# plugFeather.net
KiCad netlist of a schematic drawn in EAGLE
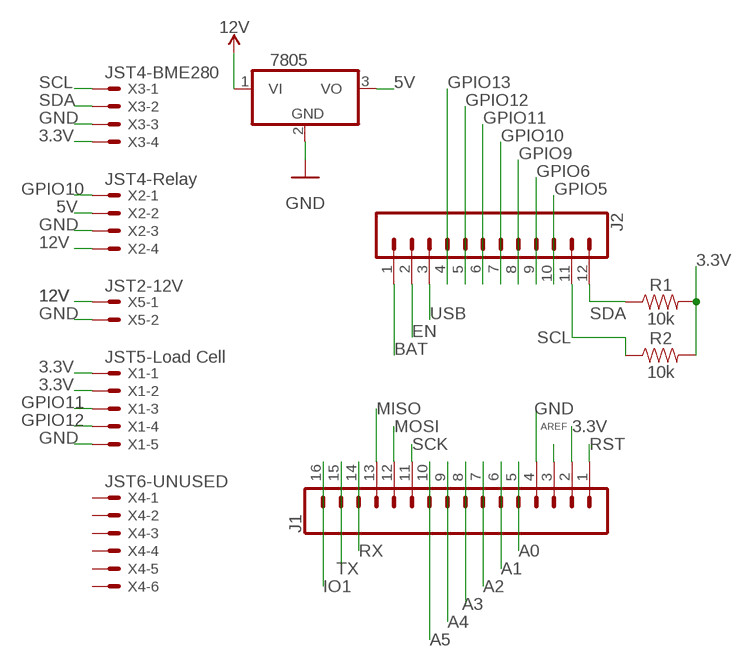
[diagram p0: schematic, sheet 1]

(export (version "E")
  (design (tool "Eeschema 10.0.6"))
  (components
    (comp (ref "IC1")
      (value "7805")
      (footprint "eagle-import:TO220V")
      (libsource (lib "eagle-import") (part "78TV05"))
    )
    (comp (ref "J1")
      (value "CONN_16")
      (footprint "eagle-import:1X16")
      (libsource (lib "eagle-import") (part "CONN_16"))
    )
    (comp (ref "J2")
      (value "CONN_12")
      (footprint "eagle-import:1X12")
      (libsource (lib "eagle-import") (part "CONN_12"))
    )
    (comp (ref "R1")
      (value "10k")
      (footprint "eagle-import:AXIAL-0.3")
      (libsource (lib "eagle-import") (part "10KOHM-HORIZ-1/4W-5%"))
    )
    (comp (ref "R2")
      (value "10k")
      (footprint "eagle-import:AXIAL-0.3")
      (libsource (lib "eagle-import") (part "10KOHM-HORIZ-1/4W-5%"))
    )
    (comp (ref "X1")
      (value "JST5-Load Cell")
      (footprint "eagle-import:JST-XH-05-PACKAGE-LONG-PAD")
      (libsource (lib "eagle-import") (part "JST-XH-05-PIN-LONG-PAD"))
    )
    (comp (ref "X2")
      (value "JST4-Relay")
      (footprint "eagle-import:JST-XH-04-PACKAGE-LONG-PAD")
      (libsource (lib "eagle-import") (part "JST-XH-04-PIN-LONG-PAD"))
    )
    (comp (ref "X3")
      (value "JST4-BME280")
      (footprint "eagle-import:JST-XH-04-PACKAGE-LONG-PAD")
      (libsource (lib "eagle-import") (part "JST-XH-04-PIN-LONG-PAD"))
    )
    (comp (ref "X4")
      (value "JST6-UNUSED")
      (footprint "eagle-import:JST-XH-06-PACKAGE-LONG-PAD")
      (libsource (lib "eagle-import") (part "JST-XH-06-PIN-LONG-PAD"))
    )
    (comp (ref "X5")
      (value "JST2-12V")
      (footprint "eagle-import:JST-XH-02-PACKAGE-LONG-PAD")
      (libsource (lib "eagle-import") (part "JST-XH-02-PIN-LONG-PAD"))
    )
  )
  (nets
    (net (code "1") (name "/3.3V") (class "Default")
      (node (ref "J1") (pin "2") (pinfunction "2_2") (pintype "passive"))
      (node (ref "R1") (pin "P$2") (pinfunction "2_P$2") (pintype "passive"))
      (node (ref "R2") (pin "P$2") (pinfunction "2_P$2") (pintype "passive"))
      (node (ref "X1") (pin "1") (pinfunction "S_1") (pintype "passive"))
      (node (ref "X1") (pin "2") (pinfunction "S_2") (pintype "passive"))
      (node (ref "X3") (pin "4") (pinfunction "S_4") (pintype "passive"))
    )
    (net (code "2") (name "/5V") (class "Default")
      (node (ref "IC1") (pin "3") (pinfunction "VO_3") (pintype "passive"))
      (node (ref "X2") (pin "2") (pinfunction "S_2") (pintype "passive"))
    )
    (net (code "3") (name "/A0") (class "Default")
      (node (ref "J1") (pin "5") (pinfunction "5_5") (pintype "passive"))
    )
    (net (code "4") (name "/A1") (class "Default")
      (node (ref "J1") (pin "6") (pinfunction "6_6") (pintype "passive"))
    )
    (net (code "5") (name "/A2") (class "Default")
      (node (ref "J1") (pin "7") (pinfunction "7_7") (pintype "passive"))
    )
    (net (code "6") (name "/A3") (class "Default")
      (node (ref "J1") (pin "8") (pinfunction "8_8") (pintype "passive"))
    )
    (net (code "7") (name "/A4") (class "Default")
      (node (ref "J1") (pin "9") (pinfunction "9_9") (pintype "passive"))
    )
    (net (code "8") (name "/A5") (class "Default")
      (node (ref "J1") (pin "10") (pinfunction "10_10") (pintype "passive"))
    )
    (net (code "9") (name "/AREF") (class "Default")
      (node (ref "J1") (pin "3") (pinfunction "3_3") (pintype "passive"))
    )
    (net (code "10") (name "/BAT") (class "Default")
      (node (ref "J2") (pin "1") (pinfunction "1_1") (pintype "passive"))
    )
    (net (code "11") (name "/EN") (class "Default")
      (node (ref "J2") (pin "2") (pinfunction "2_2") (pintype "passive"))
    )
    (net (code "12") (name "/GPIO5") (class "Default")
      (node (ref "J2") (pin "10") (pinfunction "10_10") (pintype "passive"))
    )
    (net (code "13") (name "/GPIO6") (class "Default")
      (node (ref "J2") (pin "9") (pinfunction "9_9") (pintype "passive"))
    )
    (net (code "14") (name "/GPIO9") (class "Default")
      (node (ref "J2") (pin "8") (pinfunction "8_8") (pintype "passive"))
    )
    (net (code "15") (name "/GPIO10") (class "Default")
      (node (ref "J2") (pin "7") (pinfunction "7_7") (pintype "passive"))
      (node (ref "X2") (pin "1") (pinfunction "S_1") (pintype "passive"))
    )
    (net (code "16") (name "/GPIO11") (class "Default")
      (node (ref "J2") (pin "6") (pinfunction "6_6") (pintype "passive"))
      (node (ref "X1") (pin "3") (pinfunction "S_3") (pintype "passive"))
    )
    (net (code "17") (name "/GPIO12") (class "Default")
      (node (ref "J2") (pin "5") (pinfunction "5_5") (pintype "passive"))
      (node (ref "X1") (pin "4") (pinfunction "S_4") (pintype "passive"))
    )
    (net (code "18") (name "/GPIO13") (class "Default")
      (node (ref "J2") (pin "4") (pinfunction "4_4") (pintype "passive"))
    )
    (net (code "19") (name "/IO1") (class "Default")
      (node (ref "J1") (pin "16") (pinfunction "16_16") (pintype "passive"))
    )
    (net (code "20") (name "/MISO") (class "Default")
      (node (ref "J1") (pin "13") (pinfunction "13_13") (pintype "passive"))
    )
    (net (code "21") (name "/MOSI") (class "Default")
      (node (ref "J1") (pin "12") (pinfunction "12_12") (pintype "passive"))
    )
    (net (code "22") (name "/RST") (class "Default")
      (node (ref "J1") (pin "1") (pinfunction "1_1") (pintype "passive"))
    )
    (net (code "23") (name "/RX") (class "Default")
      (node (ref "J1") (pin "14") (pinfunction "14_14") (pintype "passive"))
    )
    (net (code "24") (name "/SCK") (class "Default")
      (node (ref "J1") (pin "11") (pinfunction "11_11") (pintype "passive"))
    )
    (net (code "25") (name "/SCL") (class "Default")
      (node (ref "J2") (pin "11") (pinfunction "11_11") (pintype "passive"))
      (node (ref "R2") (pin "P$1") (pinfunction "1_P$1") (pintype "passive"))
      (node (ref "X3") (pin "1") (pinfunction "S_1") (pintype "passive"))
    )
    (net (code "26") (name "/SDA") (class "Default")
      (node (ref "J2") (pin "12") (pinfunction "12_12") (pintype "passive"))
      (node (ref "R1") (pin "P$1") (pinfunction "1_P$1") (pintype "passive"))
      (node (ref "X3") (pin "2") (pinfunction "S_2") (pintype "passive"))
    )
    (net (code "27") (name "/TX") (class "Default")
      (node (ref "J1") (pin "15") (pinfunction "15_15") (pintype "passive"))
    )
    (net (code "28") (name "/USB") (class "Default")
      (node (ref "J2") (pin "3") (pinfunction "3_3") (pintype "passive"))
    )
    (net (code "29") (name "12V") (class "Default")
      (node (ref "IC1") (pin "1") (pinfunction "VI_1") (pintype "input"))
      (node (ref "X2") (pin "4") (pinfunction "S_4") (pintype "passive"))
      (node (ref "X5") (pin "1") (pinfunction "S_1") (pintype "passive"))
    )
    (net (code "30") (name "GND") (class "Default")
      (node (ref "IC1") (pin "2") (pinfunction "GND_2") (pintype "passive"))
      (node (ref "J1") (pin "4") (pinfunction "4_4") (pintype "passive"))
      (node (ref "X1") (pin "5") (pinfunction "S_5") (pintype "passive"))
      (node (ref "X2") (pin "3") (pinfunction "S_3") (pintype "passive"))
      (node (ref "X3") (pin "3") (pinfunction "S_3") (pintype "passive"))
      (node (ref "X5") (pin "2") (pinfunction "S_2") (pintype "passive"))
    )
    (net (code "31") (name "unconnected-(X4A-S-Pad1)") (class "Default")
      (node (ref "X4") (pin "1") (pinfunction "S_1") (pintype "passive"))
    )
    (net (code "32") (name "unconnected-(X4B-S-Pad2)") (class "Default")
      (node (ref "X4") (pin "2") (pinfunction "S_2") (pintype "passive"))
    )
    (net (code "33") (name "unconnected-(X4C-S-Pad3)") (class "Default")
      (node (ref "X4") (pin "3") (pinfunction "S_3") (pintype "passive"))
    )
    (net (code "34") (name "unconnected-(X4D-S-Pad4)") (class "Default")
      (node (ref "X4") (pin "4") (pinfunction "S_4") (pintype "passive"))
    )
    (net (code "35") (name "unconnected-(X4E-S-Pad5)") (class "Default")
      (node (ref "X4") (pin "5") (pinfunction "S_5") (pintype "passive"))
    )
    (net (code "36") (name "unconnected-(X4F-S-Pad6)") (class "Default")
      (node (ref "X4") (pin "6") (pinfunction "S_6") (pintype "passive"))
    )
  )
)
